# avr-watch.net
KiCad netlist of a schematic drawn in EAGLE
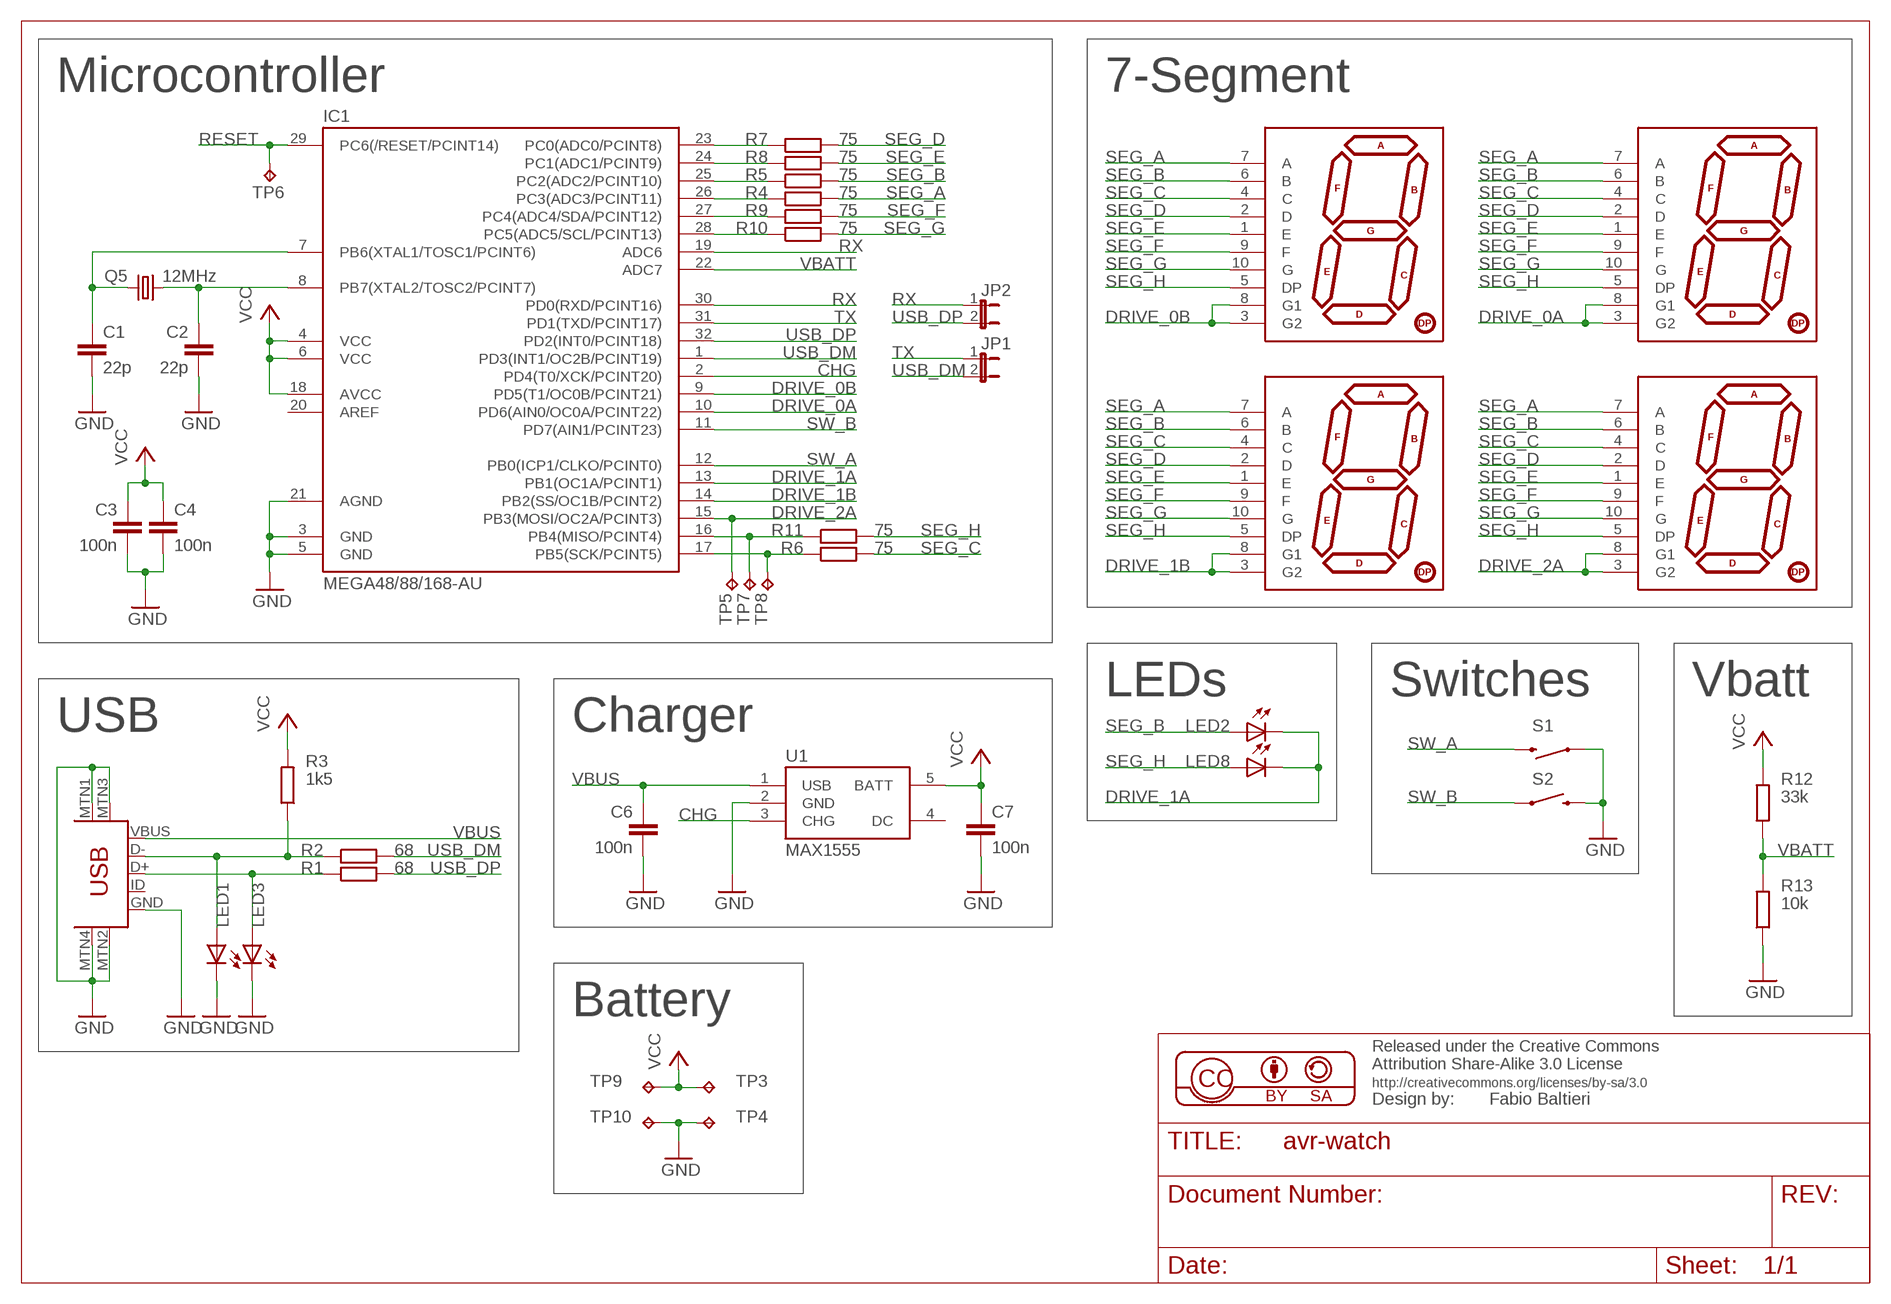
[diagram p0: schematic, sheet 1]

(export (version "E")
  (design (tool "Eeschema 10.0.6"))
  (components
    (comp (ref "C1")
      (value "22p")
      (footprint "eagle-import:C0805")
      (libsource (lib "eagle-import") (part "C-EUC0805"))
    )
    (comp (ref "C2")
      (value "22p")
      (footprint "eagle-import:C0805")
      (libsource (lib "eagle-import") (part "C-EUC0805"))
    )
    (comp (ref "C3")
      (value "100n")
      (footprint "eagle-import:C0805")
      (libsource (lib "eagle-import") (part "C-EUC0805"))
    )
    (comp (ref "C4")
      (value "100n")
      (footprint "eagle-import:C0805")
      (libsource (lib "eagle-import") (part "C-EUC0805"))
    )
    (comp (ref "C6")
      (value "100n")
      (footprint "eagle-import:C0805")
      (libsource (lib "eagle-import") (part "C-EUC0805"))
    )
    (comp (ref "C7")
      (value "100n")
      (footprint "eagle-import:C0805")
      (libsource (lib "eagle-import") (part "C-EUC0805"))
    )
    (comp (ref "IC1")
      (value "MEGA48/88/168-AU")
      (footprint "eagle-import:TQFP32-08")
      (libsource (lib "eagle-import") (part "MEGA48/88/168-AU"))
    )
    (comp (ref "JP1")
      (value "JUMPER-2SMD-NC")
      (footprint "eagle-import:SJ_2S")
      (libsource (lib "eagle-import") (part "JUMPER-2SMD-NC"))
    )
    (comp (ref "JP2")
      (value "JUMPER-2SMD-NC")
      (footprint "eagle-import:SJ_2S")
      (libsource (lib "eagle-import") (part "JUMPER-2SMD-NC"))
    )
    (comp (ref "LED1")
      (value "LEDCHIPLED_1206")
      (footprint "eagle-import:CHIPLED_1206")
      (libsource (lib "eagle-import") (part "LEDCHIPLED_1206"))
    )
    (comp (ref "LED2")
      (value "LEDCHIPLED_1206")
      (footprint "eagle-import:CHIPLED_1206")
      (libsource (lib "eagle-import") (part "LEDCHIPLED_1206"))
    )
    (comp (ref "LED3")
      (value "LEDCHIPLED_1206")
      (footprint "eagle-import:CHIPLED_1206")
      (libsource (lib "eagle-import") (part "LEDCHIPLED_1206"))
    )
    (comp (ref "LED8")
      (value "LEDCHIPLED_1206")
      (footprint "eagle-import:CHIPLED_1206")
      (libsource (lib "eagle-import") (part "LEDCHIPLED_1206"))
    )
    (comp (ref "Q5")
      (value "12MHz")
      (footprint "eagle-import:CTS406")
      (libsource (lib "eagle-import") (part "CRYSTALCTS406"))
    )
    (comp (ref "R1")
      (value "68")
      (footprint "eagle-import:R0603")
      (libsource (lib "eagle-import") (part "R-EU_R0603"))
    )
    (comp (ref "R2")
      (value "68")
      (footprint "eagle-import:R0603")
      (libsource (lib "eagle-import") (part "R-EU_R0603"))
    )
    (comp (ref "R3")
      (value "1k5")
      (footprint "eagle-import:R0603")
      (libsource (lib "eagle-import") (part "R-EU_R0603"))
    )
    (comp (ref "R4")
      (value "75")
      (footprint "eagle-import:R0603")
      (libsource (lib "eagle-import") (part "R-EU_R0603"))
    )
    (comp (ref "R5")
      (value "75")
      (footprint "eagle-import:R0603")
      (libsource (lib "eagle-import") (part "R-EU_R0603"))
    )
    (comp (ref "R6")
      (value "75")
      (footprint "eagle-import:R0603")
      (libsource (lib "eagle-import") (part "R-EU_R0603"))
    )
    (comp (ref "R7")
      (value "75")
      (footprint "eagle-import:R0603")
      (libsource (lib "eagle-import") (part "R-EU_R0603"))
    )
    (comp (ref "R8")
      (value "75")
      (footprint "eagle-import:R0603")
      (libsource (lib "eagle-import") (part "R-EU_R0603"))
    )
    (comp (ref "R9")
      (value "75")
      (footprint "eagle-import:R0603")
      (libsource (lib "eagle-import") (part "R-EU_R0603"))
    )
    (comp (ref "R10")
      (value "75")
      (footprint "eagle-import:R0603")
      (libsource (lib "eagle-import") (part "R-EU_R0603"))
    )
    (comp (ref "R11")
      (value "75")
      (footprint "eagle-import:R0603")
      (libsource (lib "eagle-import") (part "R-EU_R0603"))
    )
    (comp (ref "R12")
      (value "33k")
      (footprint "eagle-import:R0603")
      (libsource (lib "eagle-import") (part "R-EU_R0603"))
    )
    (comp (ref "R13")
      (value "10k")
      (footprint "eagle-import:R0603")
      (libsource (lib "eagle-import") (part "R-EU_R0603"))
    )
    (comp (ref "S1")
      (value "SWITCH-MOMENTARY-2SMD")
      (footprint "eagle-import:TACTILE_SWITCH_SMD")
      (libsource (lib "eagle-import") (part "SWITCH-MOMENTARY-2SMD"))
    )
    (comp (ref "S2")
      (value "SWITCH-MOMENTARY-2SMD")
      (footprint "eagle-import:TACTILE_SWITCH_SMD")
      (libsource (lib "eagle-import") (part "SWITCH-MOMENTARY-2SMD"))
    )
    (comp (ref "TP3")
      (value "TPB1,27")
      (footprint "eagle-import:B1,27")
      (libsource (lib "eagle-import") (part "TPB1,27"))
    )
    (comp (ref "TP4")
      (value "TPB1,27")
      (footprint "eagle-import:B1,27")
      (libsource (lib "eagle-import") (part "TPB1,27"))
    )
    (comp (ref "TP5")
      (value "TPTP08R")
      (footprint "eagle-import:TP08R")
      (libsource (lib "eagle-import") (part "TPTP08R"))
    )
    (comp (ref "TP6")
      (value "TPTP08R")
      (footprint "eagle-import:TP08R")
      (libsource (lib "eagle-import") (part "TPTP08R"))
    )
    (comp (ref "TP7")
      (value "TPTP08R")
      (footprint "eagle-import:TP08R")
      (libsource (lib "eagle-import") (part "TPTP08R"))
    )
    (comp (ref "TP8")
      (value "TPTP08R")
      (footprint "eagle-import:TP08R")
      (libsource (lib "eagle-import") (part "TPTP08R"))
    )
    (comp (ref "TP9")
      (value "TPTP08R")
      (footprint "eagle-import:TP08R")
      (libsource (lib "eagle-import") (part "TPTP08R"))
    )
    (comp (ref "TP10")
      (value "TPTP08R")
      (footprint "eagle-import:TP08R")
      (libsource (lib "eagle-import") (part "TPTP08R"))
    )
    (comp (ref "U$1")
      (value "7-SEGMENT-DISPLAY-1\"-RED")
      (footprint "eagle-import:7-SEGMENT-SMD")
      (libsource (lib "eagle-import") (part "7-SEGMENT-DISPLAY-1{dblquote}-RED"))
    )
    (comp (ref "U$2")
      (value "USB-MINIB-5PIN")
      (footprint "eagle-import:USB-MINIB")
      (libsource (lib "eagle-import") (part "USB-MINIB-5PIN"))
    )
    (comp (ref "U$3")
      (value "7-SEGMENT-DISPLAY-1\"-RED")
      (footprint "eagle-import:7-SEGMENT-SMD")
      (libsource (lib "eagle-import") (part "7-SEGMENT-DISPLAY-1{dblquote}-RED"))
    )
    (comp (ref "U$4")
      (value "7-SEGMENT-DISPLAY-1\"-RED")
      (footprint "eagle-import:7-SEGMENT-SMD")
      (libsource (lib "eagle-import") (part "7-SEGMENT-DISPLAY-1{dblquote}-RED"))
    )
    (comp (ref "U$5")
      (value "7-SEGMENT-DISPLAY-1\"-RED")
      (footprint "eagle-import:7-SEGMENT-SMD")
      (libsource (lib "eagle-import") (part "7-SEGMENT-DISPLAY-1{dblquote}-RED"))
    )
    (comp (ref "U1")
      (value "MAX1555")
      (footprint "eagle-import:SOT23-5")
      (libsource (lib "eagle-import") (part "MAX1555"))
    )
  )
  (nets
    (net (code "1") (name "/CHG") (class "Default")
      (node (ref "IC1") (pin "2") (pinfunction "PD4(T0/XCK/PCINT20)_2") (pintype "bidirectional"))
      (node (ref "U1") (pin "3") (pinfunction "CHG_3") (pintype "bidirectional"))
    )
    (net (code "2") (name "/DRIVE_0A") (class "Default")
      (node (ref "IC1") (pin "10") (pinfunction "PD6(AIN0/OC0A/PCINT22)_10") (pintype "bidirectional"))
      (node (ref "U$3") (pin "3") (pinfunction "G2_3") (pintype "bidirectional"))
      (node (ref "U$3") (pin "8") (pinfunction "G1_8") (pintype "bidirectional"))
    )
    (net (code "3") (name "/DRIVE_0B") (class "Default")
      (node (ref "IC1") (pin "9") (pinfunction "PD5(T1/OC0B/PCINT21)_9") (pintype "bidirectional"))
      (node (ref "U$1") (pin "3") (pinfunction "G2_3") (pintype "bidirectional"))
      (node (ref "U$1") (pin "8") (pinfunction "G1_8") (pintype "bidirectional"))
    )
    (net (code "4") (name "/DRIVE_1A") (class "Default")
      (node (ref "IC1") (pin "13") (pinfunction "PB1(OC1A/PCINT1)_13") (pintype "bidirectional"))
      (node (ref "LED2") (pin "C") (pinfunction "C_C") (pintype "passive"))
      (node (ref "LED8") (pin "C") (pinfunction "C_C") (pintype "passive"))
    )
    (net (code "5") (name "/DRIVE_1B") (class "Default")
      (node (ref "IC1") (pin "14") (pinfunction "PB2(SS/OC1B/PCINT2)_14") (pintype "bidirectional"))
      (node (ref "U$4") (pin "3") (pinfunction "G2_3") (pintype "bidirectional"))
      (node (ref "U$4") (pin "8") (pinfunction "G1_8") (pintype "bidirectional"))
    )
    (net (code "6") (name "/DRIVE_2A") (class "Default")
      (node (ref "IC1") (pin "15") (pinfunction "PB3(MOSI/OC2A/PCINT3)_15") (pintype "bidirectional"))
      (node (ref "TP5") (pin "TP") (pinfunction "TP_TP") (pintype "input"))
      (node (ref "U$5") (pin "3") (pinfunction "G2_3") (pintype "bidirectional"))
      (node (ref "U$5") (pin "8") (pinfunction "G1_8") (pintype "bidirectional"))
    )
    (net (code "7") (name "/RESET") (class "Default")
      (node (ref "IC1") (pin "29") (pinfunction "PC6(/RESET/PCINT14)_29") (pintype "bidirectional"))
      (node (ref "TP6") (pin "TP") (pinfunction "TP_TP") (pintype "input"))
    )
    (net (code "8") (name "/RX") (class "Default")
      (node (ref "IC1") (pin "19") (pinfunction "ADC6_19") (pintype "passive"))
      (node (ref "IC1") (pin "30") (pinfunction "PD0(RXD/PCINT16)_30") (pintype "bidirectional"))
      (node (ref "JP2") (pin "1") (pinfunction "1_1") (pintype "passive"))
    )
    (net (code "9") (name "/SEG_A") (class "Default")
      (node (ref "R4") (pin "2") (pinfunction "2_2") (pintype "passive"))
      (node (ref "U$1") (pin "7") (pinfunction "A_7") (pintype "bidirectional"))
      (node (ref "U$3") (pin "7") (pinfunction "A_7") (pintype "bidirectional"))
      (node (ref "U$4") (pin "7") (pinfunction "A_7") (pintype "bidirectional"))
      (node (ref "U$5") (pin "7") (pinfunction "A_7") (pintype "bidirectional"))
    )
    (net (code "10") (name "/SEG_B") (class "Default")
      (node (ref "LED2") (pin "A") (pinfunction "A_A") (pintype "passive"))
      (node (ref "R5") (pin "2") (pinfunction "2_2") (pintype "passive"))
      (node (ref "U$1") (pin "6") (pinfunction "B_6") (pintype "bidirectional"))
      (node (ref "U$3") (pin "6") (pinfunction "B_6") (pintype "bidirectional"))
      (node (ref "U$4") (pin "6") (pinfunction "B_6") (pintype "bidirectional"))
      (node (ref "U$5") (pin "6") (pinfunction "B_6") (pintype "bidirectional"))
    )
    (net (code "11") (name "/SEG_C") (class "Default")
      (node (ref "R6") (pin "2") (pinfunction "2_2") (pintype "passive"))
      (node (ref "U$1") (pin "4") (pinfunction "C_4") (pintype "bidirectional"))
      (node (ref "U$3") (pin "4") (pinfunction "C_4") (pintype "bidirectional"))
      (node (ref "U$4") (pin "4") (pinfunction "C_4") (pintype "bidirectional"))
      (node (ref "U$5") (pin "4") (pinfunction "C_4") (pintype "bidirectional"))
    )
    (net (code "12") (name "/SEG_D") (class "Default")
      (node (ref "R7") (pin "2") (pinfunction "2_2") (pintype "passive"))
      (node (ref "U$1") (pin "2") (pinfunction "D_2") (pintype "bidirectional"))
      (node (ref "U$3") (pin "2") (pinfunction "D_2") (pintype "bidirectional"))
      (node (ref "U$4") (pin "2") (pinfunction "D_2") (pintype "bidirectional"))
      (node (ref "U$5") (pin "2") (pinfunction "D_2") (pintype "bidirectional"))
    )
    (net (code "13") (name "/SEG_E") (class "Default")
      (node (ref "R8") (pin "2") (pinfunction "2_2") (pintype "passive"))
      (node (ref "U$1") (pin "1") (pinfunction "E_1") (pintype "bidirectional"))
      (node (ref "U$3") (pin "1") (pinfunction "E_1") (pintype "bidirectional"))
      (node (ref "U$4") (pin "1") (pinfunction "E_1") (pintype "bidirectional"))
      (node (ref "U$5") (pin "1") (pinfunction "E_1") (pintype "bidirectional"))
    )
    (net (code "14") (name "/SEG_F") (class "Default")
      (node (ref "R9") (pin "2") (pinfunction "2_2") (pintype "passive"))
      (node (ref "U$1") (pin "9") (pinfunction "F_9") (pintype "bidirectional"))
      (node (ref "U$3") (pin "9") (pinfunction "F_9") (pintype "bidirectional"))
      (node (ref "U$4") (pin "9") (pinfunction "F_9") (pintype "bidirectional"))
      (node (ref "U$5") (pin "9") (pinfunction "F_9") (pintype "bidirectional"))
    )
    (net (code "15") (name "/SEG_G") (class "Default")
      (node (ref "R10") (pin "2") (pinfunction "2_2") (pintype "passive"))
      (node (ref "U$1") (pin "10") (pinfunction "G_10") (pintype "bidirectional"))
      (node (ref "U$3") (pin "10") (pinfunction "G_10") (pintype "bidirectional"))
      (node (ref "U$4") (pin "10") (pinfunction "G_10") (pintype "bidirectional"))
      (node (ref "U$5") (pin "10") (pinfunction "G_10") (pintype "bidirectional"))
    )
    (net (code "16") (name "/SEG_H") (class "Default")
      (node (ref "LED8") (pin "A") (pinfunction "A_A") (pintype "passive"))
      (node (ref "R11") (pin "2") (pinfunction "2_2") (pintype "passive"))
      (node (ref "U$1") (pin "5") (pinfunction "DP_5") (pintype "bidirectional"))
      (node (ref "U$3") (pin "5") (pinfunction "DP_5") (pintype "bidirectional"))
      (node (ref "U$4") (pin "5") (pinfunction "DP_5") (pintype "bidirectional"))
      (node (ref "U$5") (pin "5") (pinfunction "DP_5") (pintype "bidirectional"))
    )
    (net (code "17") (name "/SW_A") (class "Default")
      (node (ref "IC1") (pin "12") (pinfunction "PB0(ICP1/CLKO/PCINT0)_12") (pintype "bidirectional"))
      (node (ref "S1") (pin "3") (pinfunction "2_3") (pintype "passive"))
    )
    (net (code "18") (name "/SW_B") (class "Default")
      (node (ref "IC1") (pin "11") (pinfunction "PD7(AIN1/PCINT23)_11") (pintype "bidirectional"))
      (node (ref "S2") (pin "1") (pinfunction "1_1") (pintype "passive"))
    )
    (net (code "19") (name "/TX") (class "Default")
      (node (ref "IC1") (pin "31") (pinfunction "PD1(TXD/PCINT17)_31") (pintype "bidirectional"))
      (node (ref "JP1") (pin "1") (pinfunction "1_1") (pintype "passive"))
    )
    (net (code "20") (name "/USB_DM") (class "Default")
      (node (ref "IC1") (pin "1") (pinfunction "PD3(INT1/OC2B/PCINT19)_1") (pintype "bidirectional"))
      (node (ref "JP1") (pin "2") (pinfunction "2_2") (pintype "passive"))
      (node (ref "R2") (pin "2") (pinfunction "2_2") (pintype "passive"))
    )
    (net (code "21") (name "/USB_DP") (class "Default")
      (node (ref "IC1") (pin "32") (pinfunction "PD2(INT0/PCINT18)_32") (pintype "bidirectional"))
      (node (ref "JP2") (pin "2") (pinfunction "2_2") (pintype "passive"))
      (node (ref "R1") (pin "2") (pinfunction "2_2") (pintype "passive"))
    )
    (net (code "22") (name "/VBATT") (class "Default")
      (node (ref "IC1") (pin "22") (pinfunction "ADC7_22") (pintype "passive"))
      (node (ref "R12") (pin "1") (pinfunction "1_1") (pintype "passive"))
      (node (ref "R13") (pin "2") (pinfunction "2_2") (pintype "passive"))
    )
    (net (code "23") (name "/VBUS") (class "Default")
      (node (ref "C6") (pin "1") (pinfunction "1_1") (pintype "passive"))
      (node (ref "U$2") (pin "VBUS") (pinfunction "VBUS_VBUS") (pintype "bidirectional"))
      (node (ref "U1") (pin "1") (pinfunction "USB_1") (pintype "bidirectional"))
    )
    (net (code "24") (name "GND") (class "Default")
      (node (ref "C1") (pin "2") (pinfunction "2_2") (pintype "passive"))
      (node (ref "C2") (pin "2") (pinfunction "2_2") (pintype "passive"))
      (node (ref "C3") (pin "2") (pinfunction "2_2") (pintype "passive"))
      (node (ref "C4") (pin "2") (pinfunction "2_2") (pintype "passive"))
      (node (ref "C6") (pin "2") (pinfunction "2_2") (pintype "passive"))
      (node (ref "C7") (pin "2") (pinfunction "2_2") (pintype "passive"))
      (node (ref "IC1") (pin "21") (pinfunction "AGND_21") (pintype "power_in"))
      (node (ref "IC1") (pin "3") (pinfunction "GND_3") (pintype "power_in"))
      (node (ref "IC1") (pin "5") (pinfunction "GND_5") (pintype "power_in"))
      (node (ref "LED1") (pin "C") (pinfunction "C_C") (pintype "passive"))
      (node (ref "LED3") (pin "C") (pinfunction "C_C") (pintype "passive"))
      (node (ref "R13") (pin "1") (pinfunction "1_1") (pintype "passive"))
      (node (ref "S1") (pin "1") (pinfunction "1_1") (pintype "passive"))
      (node (ref "S2") (pin "3") (pinfunction "2_3") (pintype "passive"))
      (node (ref "TP10") (pin "TP") (pinfunction "TP_TP") (pintype "input"))
      (node (ref "TP4") (pin "TP") (pinfunction "TP_TP") (pintype "input"))
      (node (ref "U$2") (pin "GND") (pinfunction "GND_GND") (pintype "bidirectional"))
      (node (ref "U$2") (pin "MTN1") (pinfunction "MTN2_MTN1") (pintype "bidirectional"))
      (node (ref "U$2") (pin "MTN2") (pinfunction "MTN3_MTN2") (pintype "bidirectional"))
      (node (ref "U$2") (pin "MTN3") (pinfunction "MTN1_MTN3") (pintype "bidirectional"))
      (node (ref "U$2") (pin "MTN4") (pinfunction "MTN4_MTN4") (pintype "bidirectional"))
      (node (ref "U1") (pin "2") (pinfunction "GND_2") (pintype "bidirectional"))
    )
    (net (code "25") (name "Net-(IC1-PB4(MISO{slash}PCINT4))") (class "Default")
      (node (ref "IC1") (pin "16") (pinfunction "PB4(MISO/PCINT4)_16") (pintype "bidirectional"))
      (node (ref "R11") (pin "1") (pinfunction "1_1") (pintype "passive"))
      (node (ref "TP7") (pin "TP") (pinfunction "TP_TP") (pintype "input"))
    )
    (net (code "26") (name "Net-(IC1-PB5(SCK{slash}PCINT5))") (class "Default")
      (node (ref "IC1") (pin "17") (pinfunction "PB5(SCK/PCINT5)_17") (pintype "bidirectional"))
      (node (ref "R6") (pin "1") (pinfunction "1_1") (pintype "passive"))
      (node (ref "TP8") (pin "TP") (pinfunction "TP_TP") (pintype "input"))
    )
    (net (code "27") (name "Net-(IC1-PB6(XTAL1{slash}TOSC1{slash}PCINT6))") (class "Default")
      (node (ref "C1") (pin "1") (pinfunction "1_1") (pintype "passive"))
      (node (ref "IC1") (pin "7") (pinfunction "PB6(XTAL1/TOSC1/PCINT6)_7") (pintype "bidirectional"))
      (node (ref "Q5") (pin "1") (pinfunction "1_1") (pintype "passive"))
    )
    (net (code "28") (name "Net-(IC1-PB7(XTAL2{slash}TOSC2{slash}PCINT7))") (class "Default")
      (node (ref "C2") (pin "1") (pinfunction "1_1") (pintype "passive"))
      (node (ref "IC1") (pin "8") (pinfunction "PB7(XTAL2/TOSC2/PCINT7)_8") (pintype "bidirectional"))
      (node (ref "Q5") (pin "3") (pinfunction "2_3") (pintype "passive"))
    )
    (net (code "29") (name "Net-(IC1-PC0(ADC0{slash}PCINT8))") (class "Default")
      (node (ref "IC1") (pin "23") (pinfunction "PC0(ADC0/PCINT8)_23") (pintype "bidirectional"))
      (node (ref "R7") (pin "1") (pinfunction "1_1") (pintype "passive"))
    )
    (net (code "30") (name "Net-(IC1-PC1(ADC1{slash}PCINT9))") (class "Default")
      (node (ref "IC1") (pin "24") (pinfunction "PC1(ADC1/PCINT9)_24") (pintype "bidirectional"))
      (node (ref "R8") (pin "1") (pinfunction "1_1") (pintype "passive"))
    )
    (net (code "31") (name "Net-(IC1-PC2(ADC2{slash}PCINT10))") (class "Default")
      (node (ref "IC1") (pin "25") (pinfunction "PC2(ADC2/PCINT10)_25") (pintype "bidirectional"))
      (node (ref "R5") (pin "1") (pinfunction "1_1") (pintype "passive"))
    )
    (net (code "32") (name "Net-(IC1-PC3(ADC3{slash}PCINT11))") (class "Default")
      (node (ref "IC1") (pin "26") (pinfunction "PC3(ADC3/PCINT11)_26") (pintype "bidirectional"))
      (node (ref "R4") (pin "1") (pinfunction "1_1") (pintype "passive"))
    )
    (net (code "33") (name "Net-(IC1-PC4(ADC4{slash}SDA{slash}PCINT12))") (class "Default")
      (node (ref "IC1") (pin "27") (pinfunction "PC4(ADC4/SDA/PCINT12)_27") (pintype "bidirectional"))
      (node (ref "R9") (pin "1") (pinfunction "1_1") (pintype "passive"))
    )
    (net (code "34") (name "Net-(IC1-PC5(ADC5{slash}SCL{slash}PCINT13))") (class "Default")
      (node (ref "IC1") (pin "28") (pinfunction "PC5(ADC5/SCL/PCINT13)_28") (pintype "bidirectional"))
      (node (ref "R10") (pin "1") (pinfunction "1_1") (pintype "passive"))
    )
    (net (code "35") (name "Net-(LED1-PadA)") (class "Default")
      (node (ref "LED1") (pin "A") (pinfunction "A_A") (pintype "passive"))
      (node (ref "R2") (pin "1") (pinfunction "1_1") (pintype "passive"))
      (node (ref "R3") (pin "1") (pinfunction "1_1") (pintype "passive"))
      (node (ref "U$2") (pin "D-") (pinfunction "D-_D-") (pintype "bidirectional"))
    )
    (net (code "36") (name "Net-(LED3-PadA)") (class "Default")
      (node (ref "LED3") (pin "A") (pinfunction "A_A") (pintype "passive"))
      (node (ref "R1") (pin "1") (pinfunction "1_1") (pintype "passive"))
      (node (ref "U$2") (pin "D+") (pinfunction "D+_D+") (pintype "bidirectional"))
    )
    (net (code "37") (name "VCC") (class "Default")
      (node (ref "C3") (pin "1") (pinfunction "1_1") (pintype "passive"))
      (node (ref "C4") (pin "1") (pinfunction "1_1") (pintype "passive"))
      (node (ref "C7") (pin "1") (pinfunction "1_1") (pintype "passive"))
      (node (ref "IC1") (pin "18") (pinfunction "AVCC_18") (pintype "passive"))
      (node (ref "IC1") (pin "4") (pinfunction "VCC_4") (pintype "power_in"))
      (node (ref "IC1") (pin "6") (pinfunction "VCC_6") (pintype "power_in"))
      (node (ref "R12") (pin "2") (pinfunction "2_2") (pintype "passive"))
      (node (ref "R3") (pin "2") (pinfunction "2_2") (pintype "passive"))
      (node (ref "TP3") (pin "TP") (pinfunction "TP_TP") (pintype "input"))
      (node (ref "TP9") (pin "TP") (pinfunction "TP_TP") (pintype "input"))
      (node (ref "U1") (pin "5") (pinfunction "BATT_5") (pintype "bidirectional"))
    )
    (net (code "38") (name "unconnected-(IC1-AREF-Pad20)") (class "Default")
      (node (ref "IC1") (pin "20") (pinfunction "AREF_20") (pintype "passive"))
    )
    (net (code "39") (name "unconnected-(U$2-PadID)") (class "Default")
      (node (ref "U$2") (pin "ID") (pinfunction "ID_ID") (pintype "bidirectional"))
    )
    (net (code "40") (name "unconnected-(U1-DC-Pad4)") (class "Default")
      (node (ref "U1") (pin "4") (pinfunction "DC_4") (pintype "bidirectional"))
    )
  )
)
